# ATmegaProgramming.net
KiCad netlist of a schematic drawn in EAGLE
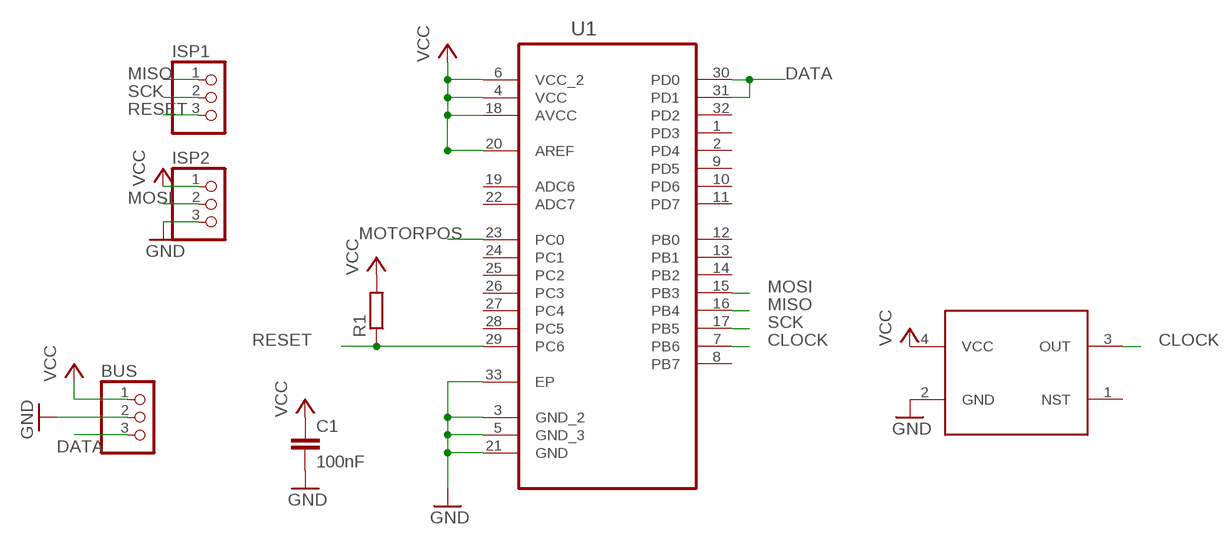
[diagram p0: schematic, sheet 1]

(export (version "E")
  (design (tool "Eeschema 10.0.6"))
  (components
    (comp (ref "BUS")
      (value "CONNEC_1X03")
      (footprint "eagle-import:CONNEC_1X03")
      (libsource (lib "eagle-import") (part "CONNEC_1X03"))
    )
    (comp (ref "C1")
      (value "100nF")
      (footprint "eagle-import:C0805")
      (libsource (lib "eagle-import") (part "C_EU-100NF"))
    )
    (comp (ref "ISP1")
      (value "CONNEC_1X03")
      (footprint "eagle-import:CONNEC_1X03")
      (libsource (lib "eagle-import") (part "CONNEC_1X03"))
    )
    (comp (ref "ISP2")
      (value "CONNEC_1X03")
      (footprint "eagle-import:CONNEC_1X03")
      (libsource (lib "eagle-import") (part "CONNEC_1X03"))
    )
    (comp (ref "R1")
      (value "RESISTANCE-R0805")
      (footprint "eagle-import:R0805")
      (libsource (lib "eagle-import") (part "RESISTANCE-R0805"))
    )
    (comp (ref "RESONATOR")
      (value "SG-310")
      (footprint "eagle-import:SG-310")
      (libsource (lib "eagle-import") (part "SG-310"))
    )
    (comp (ref "U1")
      (value "ATMEGA88PA-MU")
      (footprint "eagle-import:QFN50P500X500X100-33N")
      (libsource (lib "eagle-import") (part "ATMEGA88PA-MU"))
    )
  )
  (nets
    (net (code "1") (name "/CLOCK") (class "Default")
      (node (ref "RESONATOR") (pin "3") (pinfunction "OUT_3") (pintype "bidirectional"))
      (node (ref "U1") (pin "7") (pinfunction "PB6_7") (pintype "bidirectional"))
    )
    (net (code "2") (name "/DATA") (class "Default")
      (node (ref "BUS") (pin "3") (pinfunction "3_3") (pintype "passive"))
      (node (ref "U1") (pin "30") (pinfunction "PD0_30") (pintype "bidirectional"))
      (node (ref "U1") (pin "31") (pinfunction "PD1_31") (pintype "bidirectional"))
    )
    (net (code "3") (name "/MISO") (class "Default")
      (node (ref "ISP1") (pin "1") (pinfunction "1_1") (pintype "passive"))
      (node (ref "U1") (pin "16") (pinfunction "PB4_16") (pintype "bidirectional"))
    )
    (net (code "4") (name "/MOSI") (class "Default")
      (node (ref "ISP2") (pin "2") (pinfunction "2_2") (pintype "passive"))
      (node (ref "U1") (pin "15") (pinfunction "PB3_15") (pintype "bidirectional"))
    )
    (net (code "5") (name "/MOTORPOS") (class "Default")
      (node (ref "U1") (pin "23") (pinfunction "PC0_23") (pintype "bidirectional"))
    )
    (net (code "6") (name "/RESET") (class "Default")
      (node (ref "ISP1") (pin "3") (pinfunction "3_3") (pintype "passive"))
      (node (ref "R1") (pin "1") (pinfunction "1_1") (pintype "passive"))
      (node (ref "U1") (pin "29") (pinfunction "PC6_29") (pintype "bidirectional"))
    )
    (net (code "7") (name "/SCK") (class "Default")
      (node (ref "ISP1") (pin "2") (pinfunction "2_2") (pintype "passive"))
      (node (ref "U1") (pin "17") (pinfunction "PB5_17") (pintype "bidirectional"))
    )
    (net (code "8") (name "GND") (class "Default")
      (node (ref "BUS") (pin "2") (pinfunction "2_2") (pintype "passive"))
      (node (ref "C1") (pin "2") (pinfunction "2_2") (pintype "passive"))
      (node (ref "ISP2") (pin "3") (pinfunction "3_3") (pintype "passive"))
      (node (ref "RESONATOR") (pin "2") (pinfunction "GND_2") (pintype "bidirectional"))
      (node (ref "U1") (pin "21") (pinfunction "GND_21") (pintype "passive"))
      (node (ref "U1") (pin "3") (pinfunction "GND_2_3") (pintype "passive"))
      (node (ref "U1") (pin "33") (pinfunction "EP_33") (pintype "passive"))
      (node (ref "U1") (pin "5") (pinfunction "GND_3_5") (pintype "passive"))
    )
    (net (code "9") (name "VCC") (class "Default")
      (node (ref "BUS") (pin "1") (pinfunction "1_1") (pintype "passive"))
      (node (ref "C1") (pin "1") (pinfunction "1_1") (pintype "passive"))
      (node (ref "ISP2") (pin "1") (pinfunction "1_1") (pintype "passive"))
      (node (ref "R1") (pin "2") (pinfunction "2_2") (pintype "passive"))
      (node (ref "RESONATOR") (pin "4") (pinfunction "VCC_4") (pintype "bidirectional"))
      (node (ref "U1") (pin "18") (pinfunction "AVCC_18") (pintype "power_in"))
      (node (ref "U1") (pin "20") (pinfunction "AREF_20") (pintype "input"))
      (node (ref "U1") (pin "4") (pinfunction "VCC_4") (pintype "power_in"))
      (node (ref "U1") (pin "6") (pinfunction "VCC_2_6") (pintype "power_in"))
    )
    (net (code "10") (name "unconnected-(RESONATOR-NST-Pad1)") (class "Default")
      (node (ref "RESONATOR") (pin "1") (pinfunction "NST_1") (pintype "bidirectional"))
    )
    (net (code "11") (name "unconnected-(U1-ADC6-Pad19)") (class "Default")
      (node (ref "U1") (pin "19") (pinfunction "ADC6_19") (pintype "input"))
    )
    (net (code "12") (name "unconnected-(U1-ADC7-Pad22)") (class "Default")
      (node (ref "U1") (pin "22") (pinfunction "ADC7_22") (pintype "input"))
    )
    (net (code "13") (name "unconnected-(U1-PB0-Pad12)") (class "Default")
      (node (ref "U1") (pin "12") (pinfunction "PB0_12") (pintype "bidirectional"))
    )
    (net (code "14") (name "unconnected-(U1-PB1-Pad13)") (class "Default")
      (node (ref "U1") (pin "13") (pinfunction "PB1_13") (pintype "bidirectional"))
    )
    (net (code "15") (name "unconnected-(U1-PB2-Pad14)") (class "Default")
      (node (ref "U1") (pin "14") (pinfunction "PB2_14") (pintype "bidirectional"))
    )
    (net (code "16") (name "unconnected-(U1-PB7-Pad8)") (class "Default")
      (node (ref "U1") (pin "8") (pinfunction "PB7_8") (pintype "bidirectional"))
    )
    (net (code "17") (name "unconnected-(U1-PC1-Pad24)") (class "Default")
      (node (ref "U1") (pin "24") (pinfunction "PC1_24") (pintype "bidirectional"))
    )
    (net (code "18") (name "unconnected-(U1-PC2-Pad25)") (class "Default")
      (node (ref "U1") (pin "25") (pinfunction "PC2_25") (pintype "bidirectional"))
    )
    (net (code "19") (name "unconnected-(U1-PC3-Pad26)") (class "Default")
      (node (ref "U1") (pin "26") (pinfunction "PC3_26") (pintype "bidirectional"))
    )
    (net (code "20") (name "unconnected-(U1-PC4-Pad27)") (class "Default")
      (node (ref "U1") (pin "27") (pinfunction "PC4_27") (pintype "bidirectional"))
    )
    (net (code "21") (name "unconnected-(U1-PC5-Pad28)") (class "Default")
      (node (ref "U1") (pin "28") (pinfunction "PC5_28") (pintype "bidirectional"))
    )
    (net (code "22") (name "unconnected-(U1-PD2-Pad32)") (class "Default")
      (node (ref "U1") (pin "32") (pinfunction "PD2_32") (pintype "bidirectional"))
    )
    (net (code "23") (name "unconnected-(U1-PD3-Pad1)") (class "Default")
      (node (ref "U1") (pin "1") (pinfunction "PD3_1") (pintype "bidirectional"))
    )
    (net (code "24") (name "unconnected-(U1-PD4-Pad2)") (class "Default")
      (node (ref "U1") (pin "2") (pinfunction "PD4_2") (pintype "bidirectional"))
    )
    (net (code "25") (name "unconnected-(U1-PD5-Pad9)") (class "Default")
      (node (ref "U1") (pin "9") (pinfunction "PD5_9") (pintype "bidirectional"))
    )
    (net (code "26") (name "unconnected-(U1-PD6-Pad10)") (class "Default")
      (node (ref "U1") (pin "10") (pinfunction "PD6_10") (pintype "bidirectional"))
    )
    (net (code "27") (name "unconnected-(U1-PD7-Pad11)") (class "Default")
      (node (ref "U1") (pin "11") (pinfunction "PD7_11") (pintype "bidirectional"))
    )
  )
)
